# Loginator2368.net
KiCad netlist of a schematic drawn in EAGLE
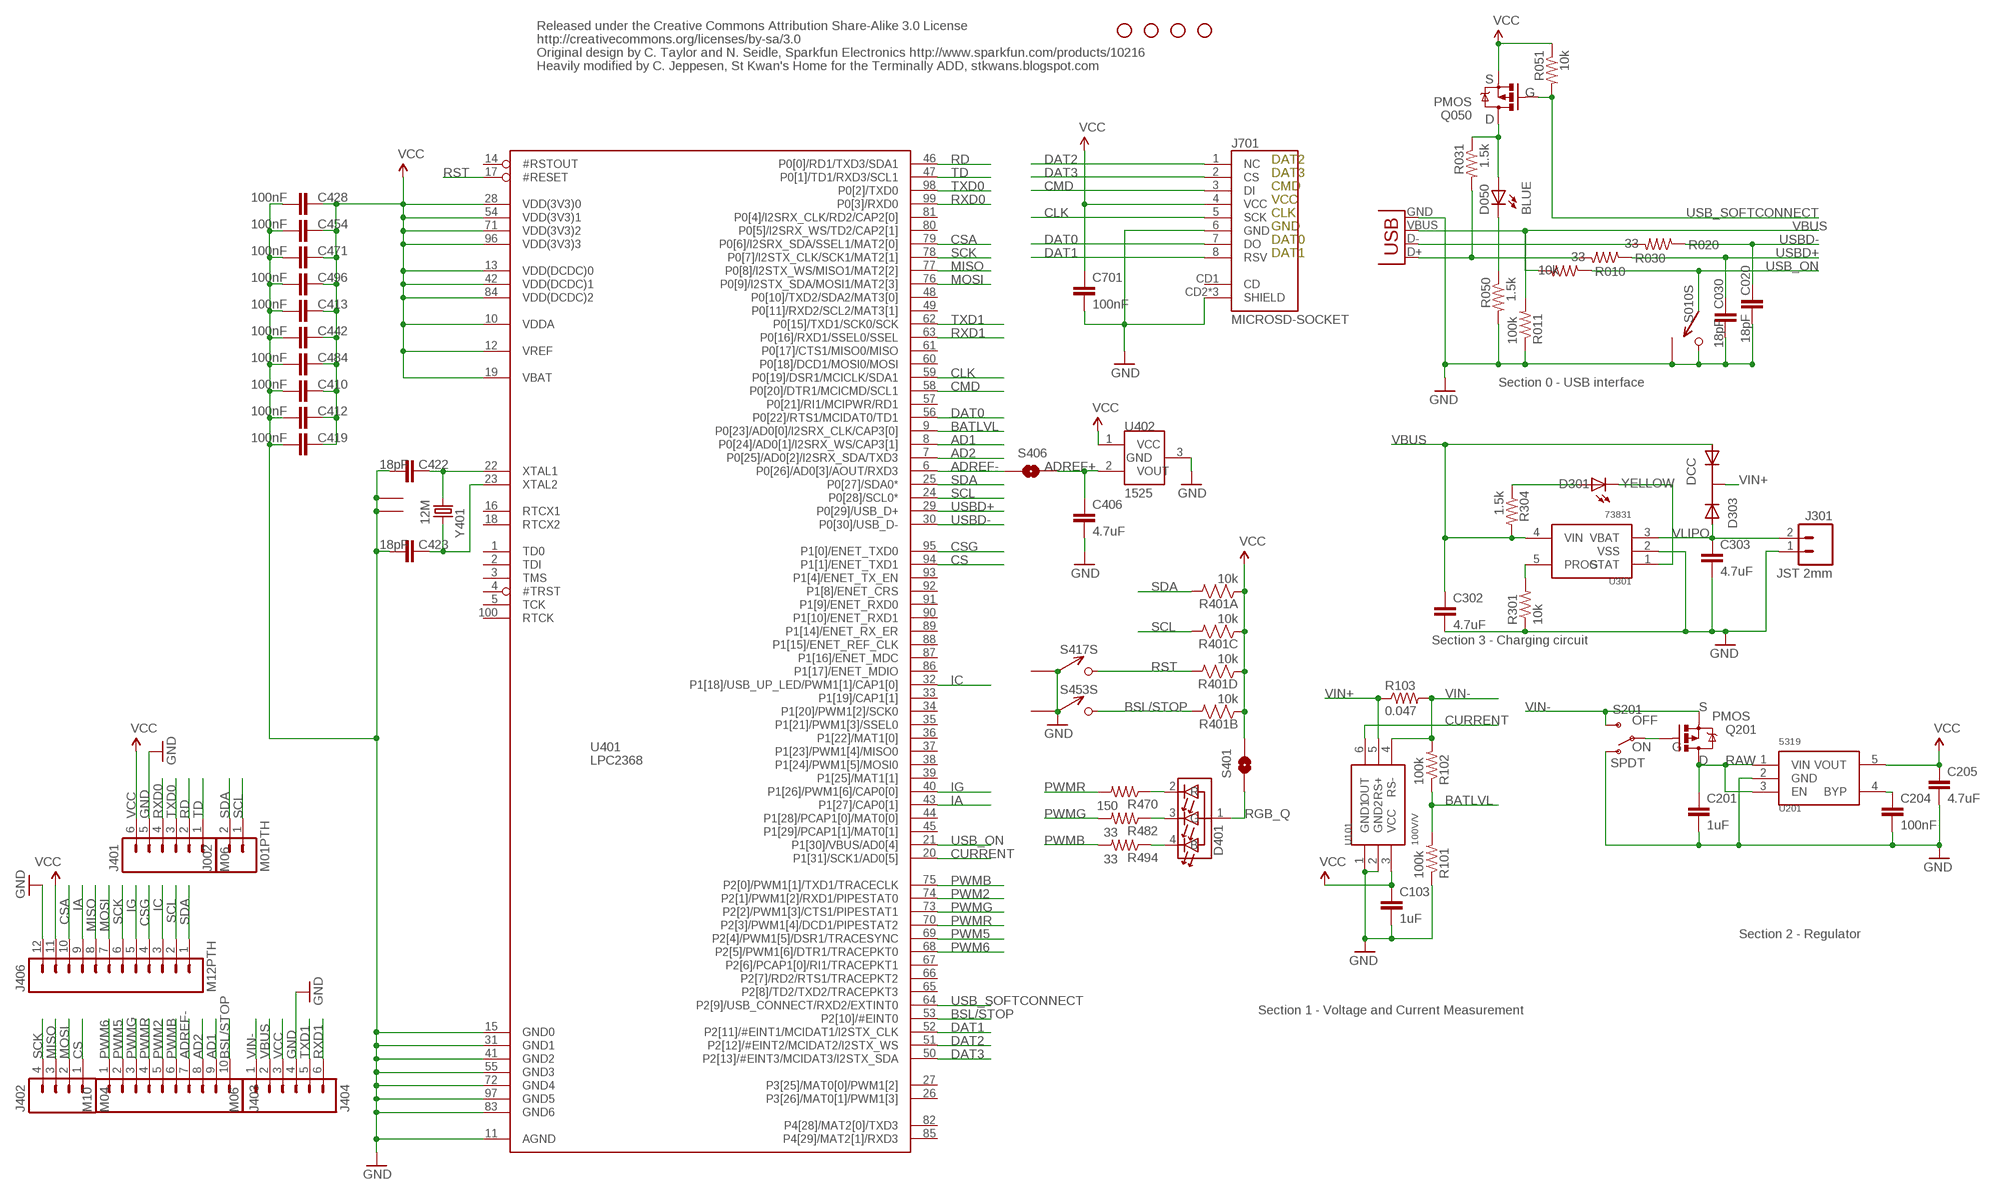
[diagram p0: schematic, sheet 1]

(export (version "E")
  (design (tool "Eeschema 10.0.6"))
  (components
    (comp (ref "C020")
      (value "18pF")
      (footprint "eagle-import:0402-CAP")
      (libsource (lib "eagle-import") (part "CAP0402-CAP"))
    )
    (comp (ref "C030")
      (value "18pF")
      (footprint "eagle-import:0402-CAP")
      (libsource (lib "eagle-import") (part "CAP0402-CAP"))
    )
    (comp (ref "C103")
      (value "1uF")
      (footprint "eagle-import:0402-CAP")
      (libsource (lib "eagle-import") (part "CAP0402-CAP"))
    )
    (comp (ref "C201")
      (value "1uF")
      (footprint "eagle-import:0402-CAP")
      (libsource (lib "eagle-import") (part "CAP0402-CAP"))
    )
    (comp (ref "C204")
      (value "100nF")
      (footprint "eagle-import:0402-CAP")
      (libsource (lib "eagle-import") (part "CAP0402-CAP"))
    )
    (comp (ref "C205")
      (value "4.7uF")
      (footprint "eagle-import:0402-CAP")
      (libsource (lib "eagle-import") (part "CAP0402-CAP"))
    )
    (comp (ref "C302")
      (value "4.7uF")
      (footprint "eagle-import:0402-CAP")
      (libsource (lib "eagle-import") (part "CAP0402-CAP"))
    )
    (comp (ref "C303")
      (value "4.7uF")
      (footprint "eagle-import:0402-CAP")
      (libsource (lib "eagle-import") (part "CAP0402-CAP"))
    )
    (comp (ref "C406")
      (value "4.7uF")
      (footprint "eagle-import:0402-CAP")
      (libsource (lib "eagle-import") (part "CAP0402-CAP"))
    )
    (comp (ref "C410")
      (value "100nF")
      (footprint "eagle-import:0402-CAP")
      (libsource (lib "eagle-import") (part "CAP0402-CAP"))
    )
    (comp (ref "C412")
      (value "100nF")
      (footprint "eagle-import:0402-CAP")
      (libsource (lib "eagle-import") (part "CAP0402-CAP"))
    )
    (comp (ref "C413")
      (value "100nF")
      (footprint "eagle-import:0402-CAP")
      (libsource (lib "eagle-import") (part "CAP0402-CAP"))
    )
    (comp (ref "C419")
      (value "100nF")
      (footprint "eagle-import:0402-CAP")
      (libsource (lib "eagle-import") (part "CAP0402-CAP"))
    )
    (comp (ref "C422")
      (value "18pF")
      (footprint "eagle-import:0402-CAP")
      (libsource (lib "eagle-import") (part "CAP0402-CAP"))
    )
    (comp (ref "C423")
      (value "18pF")
      (footprint "eagle-import:0402-CAP")
      (libsource (lib "eagle-import") (part "CAP0402-CAP"))
    )
    (comp (ref "C428")
      (value "100nF")
      (footprint "eagle-import:0402-CAP")
      (libsource (lib "eagle-import") (part "CAP0402-CAP"))
    )
    (comp (ref "C442")
      (value "100nF")
      (footprint "eagle-import:0402-CAP")
      (libsource (lib "eagle-import") (part "CAP0402-CAP"))
    )
    (comp (ref "C454")
      (value "100nF")
      (footprint "eagle-import:0402-CAP")
      (libsource (lib "eagle-import") (part "CAP0402-CAP"))
    )
    (comp (ref "C471")
      (value "100nF")
      (footprint "eagle-import:0402-CAP")
      (libsource (lib "eagle-import") (part "CAP0402-CAP"))
    )
    (comp (ref "C484")
      (value "100nF")
      (footprint "eagle-import:0402-CAP")
      (libsource (lib "eagle-import") (part "CAP0402-CAP"))
    )
    (comp (ref "C496")
      (value "100nF")
      (footprint "eagle-import:0402-CAP")
      (libsource (lib "eagle-import") (part "CAP0402-CAP"))
    )
    (comp (ref "C701")
      (value "100nF")
      (footprint "eagle-import:0402-CAP")
      (libsource (lib "eagle-import") (part "CAP0402-CAP"))
    )
    (comp (ref "D050")
      (value "BLUE")
      (footprint "eagle-import:LED-0603")
      (libsource (lib "eagle-import") (part "LED0603"))
    )
    (comp (ref "D301")
      (value "YELLOW")
      (footprint "eagle-import:LED-0603")
      (libsource (lib "eagle-import") (part "LED0603"))
    )
    (comp (ref "D303")
      (value "DCC")
      (footprint "eagle-import:SOT-23-3")
      (libsource (lib "eagle-import") (part "PMEG2005CT"))
    )
    (comp (ref "D401")
      (value "RGB")
      (footprint "eagle-import:HSMF-C118")
      (libsource (lib "eagle-import") (part "HSMF-C118"))
    )
    (comp (ref "J001")
      (value "USBSMD")
      (footprint "eagle-import:USB-MINIB")
      (libsource (lib "eagle-import") (part "USBSMD"))
    )
    (comp (ref "J002")
      (value "M01PTH")
      (footprint "eagle-import:1X02")
      (libsource (lib "eagle-import") (part "M02PTH"))
    )
    (comp (ref "J301")
      (value "JST 2mm")
      (footprint "eagle-import:JST-2-SMD")
      (libsource (lib "eagle-import") (part "M02-JST-2MM-SMT"))
    )
    (comp (ref "J401")
      (value "M06")
      (footprint "eagle-import:1X06")
      (libsource (lib "eagle-import") (part "M06SIP"))
    )
    (comp (ref "J402")
      (value "M04")
      (footprint "eagle-import:1X04")
      (libsource (lib "eagle-import") (part "M04PTH"))
    )
    (comp (ref "J403")
      (value "M10")
      (footprint "eagle-import:1X10")
      (libsource (lib "eagle-import") (part "M10{dblquote}"))
    )
    (comp (ref "J404")
      (value "M06")
      (footprint "eagle-import:1X06")
      (libsource (lib "eagle-import") (part "M06SIP"))
    )
    (comp (ref "J406")
      (value "M12PTH")
      (footprint "eagle-import:1X12")
      (libsource (lib "eagle-import") (part "M12PTH"))
    )
    (comp (ref "J701")
      (value "MICROSD-SOCKET")
      (footprint "eagle-import:MICROSD-SOCKET-PP")
      (libsource (lib "eagle-import") (part "MICROSD-SOCKET"))
    )
    (comp (ref "JP1")
      (value "STAND-OFF")
      (footprint "eagle-import:STAND-OFF")
      (libsource (lib "eagle-import") (part "STAND-OFF"))
    )
    (comp (ref "JP2")
      (value "STAND-OFF")
      (footprint "eagle-import:STAND-OFF")
      (libsource (lib "eagle-import") (part "STAND-OFF"))
    )
    (comp (ref "JP3")
      (value "STAND-OFF")
      (footprint "eagle-import:STAND-OFF")
      (libsource (lib "eagle-import") (part "STAND-OFF"))
    )
    (comp (ref "JP4")
      (value "STAND-OFF")
      (footprint "eagle-import:STAND-OFF")
      (libsource (lib "eagle-import") (part "STAND-OFF"))
    )
    (comp (ref "Q050")
      (value "PMOS")
      (footprint "eagle-import:SOT23-3")
      (libsource (lib "eagle-import") (part "MOSFET-PCHANNELSMD"))
    )
    (comp (ref "Q201")
      (value "PMOS")
      (footprint "eagle-import:SOT23-3")
      (libsource (lib "eagle-import") (part "MOSFET-PCHANNELSMD"))
    )
    (comp (ref "R010")
      (value "10k")
      (footprint "eagle-import:0402-RES")
      (libsource (lib "eagle-import") (part "RESISTOR0402-RES"))
    )
    (comp (ref "R011")
      (value "100k")
      (footprint "eagle-import:0402-RES")
      (libsource (lib "eagle-import") (part "RESISTOR0402-RES"))
    )
    (comp (ref "R020")
      (value "33")
      (footprint "eagle-import:0402-RES")
      (libsource (lib "eagle-import") (part "RESISTOR0402-RES"))
    )
    (comp (ref "R030")
      (value "33")
      (footprint "eagle-import:0402-RES")
      (libsource (lib "eagle-import") (part "RESISTOR0402-RES"))
    )
    (comp (ref "R031")
      (value "1.5k")
      (footprint "eagle-import:0402-RES")
      (libsource (lib "eagle-import") (part "RESISTOR0402-RES"))
    )
    (comp (ref "R050")
      (value "1.5k")
      (footprint "eagle-import:0402-RES")
      (libsource (lib "eagle-import") (part "RESISTOR0402-RES"))
    )
    (comp (ref "R051")
      (value "10k")
      (footprint "eagle-import:0402-RES")
      (libsource (lib "eagle-import") (part "RESISTOR0402-RES"))
    )
    (comp (ref "R101")
      (value "100k")
      (footprint "eagle-import:0402-RES")
      (libsource (lib "eagle-import") (part "RESISTOR0402-RES"))
    )
    (comp (ref "R102")
      (value "100k")
      (footprint "eagle-import:0402-RES")
      (libsource (lib "eagle-import") (part "RESISTOR0402-RES"))
    )
    (comp (ref "R103")
      (value "0.047")
      (footprint "eagle-import:0402-RES")
      (libsource (lib "eagle-import") (part "RESISTOR0402-RES"))
    )
    (comp (ref "R301")
      (value "10k")
      (footprint "eagle-import:0402-RES")
      (libsource (lib "eagle-import") (part "RESISTOR0402-RES"))
    )
    (comp (ref "R304")
      (value "1.5k")
      (footprint "eagle-import:0402-RES")
      (libsource (lib "eagle-import") (part "RESISTOR0402-RES"))
    )
    (comp (ref "R401")
      (value "10k")
      (footprint "eagle-import:CRA04")
      (libsource (lib "eagle-import") (part "RP404"))
    )
    (comp (ref "R470")
      (value "150")
      (footprint "eagle-import:0402-RES")
      (libsource (lib "eagle-import") (part "RESISTOR0402-RES"))
    )
    (comp (ref "R482")
      (value "33")
      (footprint "eagle-import:0402-RES")
      (libsource (lib "eagle-import") (part "RESISTOR0402-RES"))
    )
    (comp (ref "R494")
      (value "33")
      (footprint "eagle-import:0402-RES")
      (libsource (lib "eagle-import") (part "RESISTOR0402-RES"))
    )
    (comp (ref "S010")
      (value "SPST")
      (footprint "eagle-import:B3U-1100P")
      (libsource (lib "eagle-import") (part "B3U-1100P"))
    )
    (comp (ref "S201")
      (value "SPDT")
      (footprint "eagle-import:AYZ0202")
      (libsource (lib "eagle-import") (part "SWITCH-SPSTSMD"))
    )
    (comp (ref "S401")
      (value "SOLDERJUMPERNO")
      (footprint "eagle-import:SJ_2S-NO")
      (libsource (lib "eagle-import") (part "SOLDERJUMPERNO"))
    )
    (comp (ref "S406")
      (value "SOLDERJUMPERNO")
      (footprint "eagle-import:SJ_2S-NO")
      (libsource (lib "eagle-import") (part "SOLDERJUMPERNO"))
    )
    (comp (ref "S417")
      (value "SPST")
      (footprint "eagle-import:B3U-1100P")
      (libsource (lib "eagle-import") (part "B3U-1100P"))
    )
    (comp (ref "S453")
      (value "SPST")
      (footprint "eagle-import:B3U-1100P")
      (libsource (lib "eagle-import") (part "B3U-1100P"))
    )
    (comp (ref "U101")
      (value "100V/V")
      (footprint "eagle-import:SOT-23-6")
      (libsource (lib "eagle-import") (part "MAX4173"))
    )
    (comp (ref "U201")
      (value "5319")
      (footprint "eagle-import:SOT-23-5")
      (libsource (lib "eagle-import") (part "MIC5319D5"))
    )
    (comp (ref "U301")
      (value "73831")
      (footprint "eagle-import:SOT-23-5")
      (libsource (lib "eagle-import") (part "MCP73831"))
    )
    (comp (ref "U401")
      (value "LPC2368")
      (footprint "eagle-import:LQFP100")
      (libsource (lib "eagle-import") (part "LPC2368"))
    )
    (comp (ref "U402")
      (value "1525")
      (footprint "eagle-import:SOT-23-3")
      (libsource (lib "eagle-import") (part "MCP1525"))
    )
    (comp (ref "Y401")
      (value "12M")
      (footprint "eagle-import:CRYSTAL_SMD")
      (libsource (lib "eagle-import") (part "TSX-3225"))
    )
  )
  (nets
    (net (code "1") (name "/AD1") (class "Default")
      (node (ref "J403") (pin "9") (pinfunction "9_9") (pintype "passive"))
      (node (ref "U401") (pin "8") (pinfunction "P0[24]/AD0[1]/I2SRX_WS/CAP3[1]_8") (pintype "bidirectional"))
    )
    (net (code "2") (name "/AD2") (class "Default")
      (node (ref "J403") (pin "8") (pinfunction "8_8") (pintype "passive"))
      (node (ref "U401") (pin "7") (pinfunction "P0[25]/AD0[2]/I2SRX_SDA/TXD3_7") (pintype "bidirectional"))
    )
    (net (code "3") (name "/ADREF+") (class "Default")
      (node (ref "C406") (pin "1") (pinfunction "1_1") (pintype "passive"))
      (node (ref "S406") (pin "1") (pinfunction "1_1") (pintype "passive"))
      (node (ref "U402") (pin "2") (pinfunction "VOUT_2") (pintype "bidirectional"))
    )
    (net (code "4") (name "/ADREF-") (class "Default")
      (node (ref "J403") (pin "7") (pinfunction "7_7") (pintype "passive"))
      (node (ref "S406") (pin "2") (pinfunction "2_2") (pintype "passive"))
      (node (ref "U401") (pin "6") (pinfunction "P0[26]/AD0[3]/AOUT/RXD3_6") (pintype "bidirectional"))
    )
    (net (code "5") (name "/BATLVL") (class "Default")
      (node (ref "R101") (pin "2") (pinfunction "2_2") (pintype "passive"))
      (node (ref "R102") (pin "1") (pinfunction "1_1") (pintype "passive"))
      (node (ref "U401") (pin "9") (pinfunction "P0[23]/AD0[0]/I2SRX_CLK/CAP3[0]_9") (pintype "bidirectional"))
    )
    (net (code "6") (name "/BSL{slash}STOP") (class "Default")
      (node (ref "J403") (pin "10") (pinfunction "10_10") (pintype "passive"))
      (node (ref "R401") (pin "7") (pinfunction "2_7") (pintype "passive"))
      (node (ref "S453") (pin "P$2") (pinfunction "2_P$2") (pintype "bidirectional"))
      (node (ref "U401") (pin "53") (pinfunction "P2[10]/#EINT0_53") (pintype "bidirectional"))
    )
    (net (code "7") (name "/CLK") (class "Default")
      (node (ref "J701") (pin "5") (pinfunction "SCK_5") (pintype "bidirectional"))
      (node (ref "U401") (pin "59") (pinfunction "P0[19]/DSR1/MCICLK/SDA1_59") (pintype "bidirectional"))
    )
    (net (code "8") (name "/CMD") (class "Default")
      (node (ref "J701") (pin "3") (pinfunction "DI_3") (pintype "bidirectional"))
      (node (ref "U401") (pin "58") (pinfunction "P0[20]/DTR1/MCICMD/SCL1_58") (pintype "bidirectional"))
    )
    (net (code "9") (name "/CS") (class "Default")
      (node (ref "J402") (pin "1") (pinfunction "1_1") (pintype "passive"))
      (node (ref "U401") (pin "94") (pinfunction "P1[1]/ENET_TXD1_94") (pintype "bidirectional"))
    )
    (net (code "10") (name "/CSA") (class "Default")
      (node (ref "J406") (pin "10") (pinfunction "10_10") (pintype "passive"))
      (node (ref "U401") (pin "79") (pinfunction "P0[6]/I2SRX_SDA/SSEL1/MAT2[0]_79") (pintype "bidirectional"))
    )
    (net (code "11") (name "/CSG") (class "Default")
      (node (ref "J406") (pin "4") (pinfunction "4_4") (pintype "passive"))
      (node (ref "U401") (pin "95") (pinfunction "P1[0]/ENET_TXD0_95") (pintype "bidirectional"))
    )
    (net (code "12") (name "/CURRENT") (class "Default")
      (node (ref "U101") (pin "6") (pinfunction "OUT_6") (pintype "bidirectional"))
      (node (ref "U401") (pin "20") (pinfunction "P1[31]/SCK1/AD0[5]_20") (pintype "bidirectional"))
    )
    (net (code "13") (name "/DAT0") (class "Default")
      (node (ref "J701") (pin "7") (pinfunction "DO_7") (pintype "bidirectional"))
      (node (ref "U401") (pin "56") (pinfunction "P0[22]/RTS1/MCIDAT0/TD1_56") (pintype "bidirectional"))
    )
    (net (code "14") (name "/DAT1") (class "Default")
      (node (ref "J701") (pin "8") (pinfunction "RSV_8") (pintype "bidirectional"))
      (node (ref "U401") (pin "52") (pinfunction "P2[11]/#EINT1/MCIDAT1/I2STX_CLK_52") (pintype "bidirectional"))
    )
    (net (code "15") (name "/DAT2") (class "Default")
      (node (ref "J701") (pin "1") (pinfunction "NC_1") (pintype "bidirectional"))
      (node (ref "U401") (pin "51") (pinfunction "P2[12]/#EINT2/MCIDAT2/I2STX_WS_51") (pintype "bidirectional"))
    )
    (net (code "16") (name "/DAT3") (class "Default")
      (node (ref "J701") (pin "2") (pinfunction "CS_2") (pintype "bidirectional"))
      (node (ref "U401") (pin "50") (pinfunction "P2[13]/#EINT3/MCIDAT3/I2STX_SDA_50") (pintype "bidirectional"))
    )
    (net (code "17") (name "/IA") (class "Default")
      (node (ref "J406") (pin "9") (pinfunction "9_9") (pintype "passive"))
      (node (ref "U401") (pin "43") (pinfunction "P1[27]/CAP0[1]_43") (pintype "bidirectional"))
    )
    (net (code "18") (name "/IC") (class "Default")
      (node (ref "J406") (pin "3") (pinfunction "3_3") (pintype "passive"))
      (node (ref "U401") (pin "32") (pinfunction "P1[18]/USB_UP_LED/PWM1[1]/CAP1[0]_32") (pintype "bidirectional"))
    )
    (net (code "19") (name "/IG") (class "Default")
      (node (ref "J406") (pin "5") (pinfunction "5_5") (pintype "passive"))
      (node (ref "U401") (pin "40") (pinfunction "P1[26]/PWM1[6]/CAP0[0]_40") (pintype "bidirectional"))
    )
    (net (code "20") (name "/MISO") (class "Default")
      (node (ref "J402") (pin "3") (pinfunction "3_3") (pintype "passive"))
      (node (ref "J406") (pin "8") (pinfunction "8_8") (pintype "passive"))
      (node (ref "U401") (pin "77") (pinfunction "P0[8]/I2STX_WS/MISO1/MAT2[2]_77") (pintype "bidirectional"))
    )
    (net (code "21") (name "/MOSI") (class "Default")
      (node (ref "J402") (pin "2") (pinfunction "2_2") (pintype "passive"))
      (node (ref "J406") (pin "7") (pinfunction "7_7") (pintype "passive"))
      (node (ref "U401") (pin "76") (pinfunction "P0[9]/I2STX_SDA/MOSI1/MAT2[3]_76") (pintype "bidirectional"))
    )
    (net (code "22") (name "/PWM2") (class "Default")
      (node (ref "J403") (pin "5") (pinfunction "5_5") (pintype "passive"))
      (node (ref "U401") (pin "74") (pinfunction "P2[1]/PWM1[2]/RXD1/PIPESTAT0_74") (pintype "bidirectional"))
    )
    (net (code "23") (name "/PWM5") (class "Default")
      (node (ref "J403") (pin "2") (pinfunction "2_2") (pintype "passive"))
      (node (ref "U401") (pin "69") (pinfunction "P2[4]/PWM1[5]/DSR1/TRACESYNC_69") (pintype "bidirectional"))
    )
    (net (code "24") (name "/PWM6") (class "Default")
      (node (ref "J403") (pin "1") (pinfunction "1_1") (pintype "passive"))
      (node (ref "U401") (pin "68") (pinfunction "P2[5]/PWM1[6]/DTR1/TRACEPKT0_68") (pintype "bidirectional"))
    )
    (net (code "25") (name "/PWMB") (class "Default")
      (node (ref "J403") (pin "6") (pinfunction "6_6") (pintype "passive"))
      (node (ref "R494") (pin "2") (pinfunction "2_2") (pintype "passive"))
      (node (ref "U401") (pin "75") (pinfunction "P2[0]/PWM1[1]/TXD1/TRACECLK_75") (pintype "bidirectional"))
    )
    (net (code "26") (name "/PWMG") (class "Default")
      (node (ref "J403") (pin "3") (pinfunction "3_3") (pintype "passive"))
      (node (ref "R482") (pin "2") (pinfunction "2_2") (pintype "passive"))
      (node (ref "U401") (pin "73") (pinfunction "P2[2]/PWM1[3]/CTS1/PIPESTAT1_73") (pintype "bidirectional"))
    )
    (net (code "27") (name "/PWMR") (class "Default")
      (node (ref "J403") (pin "4") (pinfunction "4_4") (pintype "passive"))
      (node (ref "R470") (pin "2") (pinfunction "2_2") (pintype "passive"))
      (node (ref "U401") (pin "70") (pinfunction "P2[3]/PWM1[4]/DCD1/PIPESTAT2_70") (pintype "bidirectional"))
    )
    (net (code "28") (name "/RAW") (class "Default")
      (node (ref "C201") (pin "1") (pinfunction "1_1") (pintype "passive"))
      (node (ref "Q201") (pin "3") (pinfunction "D_3") (pintype "passive"))
      (node (ref "U201") (pin "1") (pinfunction "VIN_1") (pintype "bidirectional"))
      (node (ref "U201") (pin "3") (pinfunction "EN_3") (pintype "bidirectional"))
    )
    (net (code "29") (name "/RD") (class "Default")
      (node (ref "J401") (pin "2") (pinfunction "2_2") (pintype "passive"))
      (node (ref "U401") (pin "46") (pinfunction "P0[0]/RD1/TXD3/SDA1_46") (pintype "bidirectional"))
    )
    (net (code "30") (name "/RGB_Q") (class "Default")
      (node (ref "D401") (pin "1") (pinfunction "A_1") (pintype "passive"))
      (node (ref "S401") (pin "1") (pinfunction "1_1") (pintype "passive"))
    )
    (net (code "31") (name "/RST") (class "Default")
      (node (ref "R401") (pin "5") (pinfunction "2_5") (pintype "passive"))
      (node (ref "S417") (pin "P$2") (pinfunction "2_P$2") (pintype "bidirectional"))
      (node (ref "U401") (pin "17") (pinfunction "#RESET_17") (pintype "bidirectional"))
    )
    (net (code "32") (name "/RXD0") (class "Default")
      (node (ref "J401") (pin "4") (pinfunction "4_4") (pintype "passive"))
      (node (ref "U401") (pin "99") (pinfunction "P0[3]/RXD0_99") (pintype "bidirectional"))
    )
    (net (code "33") (name "/RXD1") (class "Default")
      (node (ref "J404") (pin "6") (pinfunction "6_6") (pintype "passive"))
      (node (ref "U401") (pin "63") (pinfunction "P0[16]/RXD1/SSEL0/SSEL_63") (pintype "bidirectional"))
    )
    (net (code "34") (name "/SCK") (class "Default")
      (node (ref "J402") (pin "4") (pinfunction "4_4") (pintype "passive"))
      (node (ref "J406") (pin "6") (pinfunction "6_6") (pintype "passive"))
      (node (ref "U401") (pin "78") (pinfunction "P0[7]/I2STX_CLK/SCK1/MAT2[1]_78") (pintype "bidirectional"))
    )
    (net (code "35") (name "/SCL") (class "Default")
      (node (ref "J002") (pin "1") (pinfunction "1_1") (pintype "passive"))
      (node (ref "J406") (pin "2") (pinfunction "2_2") (pintype "passive"))
      (node (ref "R401") (pin "6") (pinfunction "2_6") (pintype "passive"))
      (node (ref "U401") (pin "24") (pinfunction "P0[28]/SCL0*_24") (pintype "bidirectional"))
    )
    (net (code "36") (name "/SDA") (class "Default")
      (node (ref "J002") (pin "2") (pinfunction "2_2") (pintype "passive"))
      (node (ref "J406") (pin "1") (pinfunction "1_1") (pintype "passive"))
      (node (ref "R401") (pin "8") (pinfunction "2_8") (pintype "passive"))
      (node (ref "U401") (pin "25") (pinfunction "P0[27]/SDA0*_25") (pintype "bidirectional"))
    )
    (net (code "37") (name "/TD") (class "Default")
      (node (ref "J401") (pin "1") (pinfunction "1_1") (pintype "passive"))
      (node (ref "U401") (pin "47") (pinfunction "P0[1]/TD1/RXD3/SCL1_47") (pintype "bidirectional"))
    )
    (net (code "38") (name "/TXD0") (class "Default")
      (node (ref "J401") (pin "3") (pinfunction "3_3") (pintype "passive"))
      (node (ref "U401") (pin "98") (pinfunction "P0[2]/TXD0_98") (pintype "bidirectional"))
    )
    (net (code "39") (name "/TXD1") (class "Default")
      (node (ref "J404") (pin "5") (pinfunction "5_5") (pintype "passive"))
      (node (ref "U401") (pin "62") (pinfunction "P0[15]/TXD1/SCK0/SCK_62") (pintype "bidirectional"))
    )
    (net (code "40") (name "/USBD+") (class "Default")
      (node (ref "C030") (pin "1") (pinfunction "1_1") (pintype "passive"))
      (node (ref "R030") (pin "1") (pinfunction "1_1") (pintype "passive"))
      (node (ref "U401") (pin "29") (pinfunction "P0[29]/USB_D+_29") (pintype "bidirectional"))
    )
    (net (code "41") (name "/USBD-") (class "Default")
      (node (ref "C020") (pin "1") (pinfunction "1_1") (pintype "passive"))
      (node (ref "R020") (pin "1") (pinfunction "1_1") (pintype "passive"))
      (node (ref "U401") (pin "30") (pinfunction "P0[30]/USB_D-_30") (pintype "bidirectional"))
    )
    (net (code "42") (name "/USB_ON") (class "Default")
      (node (ref "R010") (pin "1") (pinfunction "1_1") (pintype "passive"))
      (node (ref "S010") (pin "P$1") (pinfunction "1_P$1") (pintype "bidirectional"))
      (node (ref "U401") (pin "21") (pinfunction "P1[30]/VBUS/AD0[4]_21") (pintype "bidirectional"))
    )
    (net (code "43") (name "/USB_SOFTCONNECT") (class "Default")
      (node (ref "Q050") (pin "1") (pinfunction "G_1") (pintype "passive"))
      (node (ref "R051") (pin "2") (pinfunction "2_2") (pintype "passive"))
      (node (ref "U401") (pin "64") (pinfunction "P2[9]/USB_CONNECT/RXD2/EXTINT0_64") (pintype "bidirectional"))
    )
    (net (code "44") (name "/VBUS") (class "Default")
      (node (ref "C302") (pin "1") (pinfunction "1_1") (pintype "passive"))
      (node (ref "D303") (pin "1") (pinfunction "A1_1") (pintype "passive"))
      (node (ref "J001") (pin "VBUS") (pinfunction "VBUS_VBUS") (pintype "bidirectional"))
      (node (ref "J404") (pin "2") (pinfunction "2_2") (pintype "passive"))
      (node (ref "R010") (pin "2") (pinfunction "2_2") (pintype "passive"))
      (node (ref "R011") (pin "2") (pinfunction "2_2") (pintype "passive"))
      (node (ref "R304") (pin "2") (pinfunction "2_2") (pintype "passive"))
      (node (ref "U301") (pin "4") (pinfunction "VIN_4") (pintype "bidirectional"))
    )
    (net (code "45") (name "/VIN+") (class "Default")
      (node (ref "D303") (pin "3") (pinfunction "K_3") (pintype "passive"))
      (node (ref "R103") (pin "1") (pinfunction "1_1") (pintype "passive"))
      (node (ref "U101") (pin "5") (pinfunction "RS+_5") (pintype "bidirectional"))
    )
    (net (code "46") (name "/VIN-") (class "Default")
      (node (ref "J404") (pin "1") (pinfunction "1_1") (pintype "passive"))
      (node (ref "Q201") (pin "2") (pinfunction "S_2") (pintype "passive"))
      (node (ref "R102") (pin "2") (pinfunction "2_2") (pintype "passive"))
      (node (ref "R103") (pin "2") (pinfunction "2_2") (pintype "passive"))
      (node (ref "S201") (pin "3") (pinfunction "S_3") (pintype "passive"))
      (node (ref "U101") (pin "4") (pinfunction "RS-_4") (pintype "bidirectional"))
    )
    (net (code "47") (name "/VLIPO") (class "Default")
      (node (ref "C303") (pin "1") (pinfunction "1_1") (pintype "passive"))
      (node (ref "D303") (pin "2") (pinfunction "A2_2") (pintype "passive"))
      (node (ref "J301") (pin "2") (pinfunction "2_2") (pintype "passive"))
      (node (ref "U301") (pin "3") (pinfunction "VBAT_3") (pintype "bidirectional"))
    )
    (net (code "48") (name "GND") (class "Default")
      (node (ref "C020") (pin "2") (pinfunction "2_2") (pintype "passive"))
      (node (ref "C030") (pin "2") (pinfunction "2_2") (pintype "passive"))
      (node (ref "C103") (pin "2") (pinfunction "2_2") (pintype "passive"))
      (node (ref "C201") (pin "2") (pinfunction "2_2") (pintype "passive"))
      (node (ref "C204") (pin "2") (pinfunction "2_2") (pintype "passive"))
      (node (ref "C205") (pin "2") (pinfunction "2_2") (pintype "passive"))
      (node (ref "C302") (pin "2") (pinfunction "2_2") (pintype "passive"))
      (node (ref "C303") (pin "2") (pinfunction "2_2") (pintype "passive"))
      (node (ref "C406") (pin "2") (pinfunction "2_2") (pintype "passive"))
      (node (ref "C410") (pin "2") (pinfunction "2_2") (pintype "passive"))
      (node (ref "C412") (pin "2") (pinfunction "2_2") (pintype "passive"))
      (node (ref "C413") (pin "2") (pinfunction "2_2") (pintype "passive"))
      (node (ref "C419") (pin "2") (pinfunction "2_2") (pintype "passive"))
      (node (ref "C422") (pin "1") (pinfunction "1_1") (pintype "passive"))
      (node (ref "C423") (pin "1") (pinfunction "1_1") (pintype "passive"))
      (node (ref "C428") (pin "2") (pinfunction "2_2") (pintype "passive"))
      (node (ref "C442") (pin "2") (pinfunction "2_2") (pintype "passive"))
      (node (ref "C454") (pin "2") (pinfunction "2_2") (pintype "passive"))
      (node (ref "C471") (pin "2") (pinfunction "2_2") (pintype "passive"))
      (node (ref "C484") (pin "2") (pinfunction "2_2") (pintype "passive"))
      (node (ref "C496") (pin "2") (pinfunction "2_2") (pintype "passive"))
      (node (ref "C701") (pin "2") (pinfunction "2_2") (pintype "passive"))
      (node (ref "J001") (pin "GND") (pinfunction "GND_GND") (pintype "bidirectional"))
      (node (ref "J301") (pin "1") (pinfunction "1_1") (pintype "passive"))
      (node (ref "J401") (pin "5") (pinfunction "5_5") (pintype "passive"))
      (node (ref "J404") (pin "4") (pinfunction "4_4") (pintype "passive"))
      (node (ref "J406") (pin "12") (pinfunction "12_12") (pintype "passive"))
      (node (ref "J701") (pin "6") (pinfunction "GND_6") (pintype "bidirectional"))
      (node (ref "J701") (pin "CD2") (pinfunction "SHIELD_CD2") (pintype "bidirectional"))
      (node (ref "J701") (pin "GND1") (pinfunction "SHIELD_GND1") (pintype "bidirectional"))
      (node (ref "J701") (pin "GND3") (pinfunction "SHIELD_GND3") (pintype "bidirectional"))
      (node (ref "R011") (pin "1") (pinfunction "1_1") (pintype "passive"))
      (node (ref "R050") (pin "2") (pinfunction "2_2") (pintype "passive"))
      (node (ref "R101") (pin "1") (pinfunction "1_1") (pintype "passive"))
      (node (ref "R301") (pin "1") (pinfunction "1_1") (pintype "passive"))
      (node (ref "S010") (pin "P$2") (pinfunction "2_P$2") (pintype "bidirectional"))
      (node (ref "S010") (pin "P$3") (pinfunction "1_P$3") (pintype "bidirectional"))
      (node (ref "S201") (pin "1") (pinfunction "O_1") (pintype "passive"))
      (node (ref "S417") (pin "P$1") (pinfunction "1_P$1") (pintype "bidirectional"))
      (node (ref "S417") (pin "P$3") (pinfunction "1_P$3") (pintype "bidirectional"))
      (node (ref "S453") (pin "P$1") (pinfunction "1_P$1") (pintype "bidirectional"))
      (node (ref "S453") (pin "P$3") (pinfunction "1_P$3") (pintype "bidirectional"))
      (node (ref "U101") (pin "1") (pinfunction "GND1_1") (pintype "bidirectional"))
      (node (ref "U101") (pin "2") (pinfunction "GND2_2") (pintype "bidirectional"))
      (node (ref "U201") (pin "2") (pinfunction "GND_2") (pintype "bidirectional"))
      (node (ref "U301") (pin "2") (pinfunction "VSS_2") (pintype "bidirectional"))
      (node (ref "U401") (pin "11") (pinfunction "AGND_11") (pintype "bidirectional"))
      (node (ref "U401") (pin "15") (pinfunction "GND0_15") (pintype "bidirectional"))
      (node (ref "U401") (pin "31") (pinfunction "GND1_31") (pintype "bidirectional"))
      (node (ref "U401") (pin "41") (pinfunction "GND2_41") (pintype "bidirectional"))
      (node (ref "U401") (pin "55") (pinfunction "GND3_55") (pintype "bidirectional"))
      (node (ref "U401") (pin "72") (pinfunction "GND4_72") (pintype "bidirectional"))
      (node (ref "U401") (pin "83") (pinfunction "GND6_83") (pintype "bidirectional"))
      (node (ref "U401") (pin "97") (pinfunction "GND5_97") (pintype "bidirectional"))
      (node (ref "U402") (pin "3") (pinfunction "GND_3") (pintype "bidirectional"))
      (node (ref "Y401") (pin "2") (pinfunction "1_2") (pintype "bidirectional"))
      (node (ref "Y401") (pin "4") (pinfunction "1_4") (pintype "bidirectional"))
    )
    (net (code "49") (name "Net-(D050-PadC)") (class "Default")
      (node (ref "D050") (pin "C") (pinfunction "C_C") (pintype "passive"))
      (node (ref "R050") (pin "1") (pinfunction "1_1") (pintype "passive"))
    )
    (net (code "50") (name "Net-(D301-PadA)") (class "Default")
      (node (ref "D301") (pin "A") (pinfunction "A_A") (pintype "passive"))
      (node (ref "R304") (pin "1") (pinfunction "1_1") (pintype "passive"))
    )
    (net (code "51") (name "Net-(D401-B)") (class "Default")
      (node (ref "D401") (pin "4") (pinfunction "B_4") (pintype "passive"))
      (node (ref "R494") (pin "1") (pinfunction "1_1") (pintype "passive"))
    )
    (net (code "52") (name "Net-(D401-G)") (class "Default")
      (node (ref "D401") (pin "3") (pinfunction "G_3") (pintype "passive"))
      (node (ref "R482") (pin "1") (pinfunction "1_1") (pintype "passive"))
    )
    (net (code "53") (name "Net-(D401-R)") (class "Default")
      (node (ref "D401") (pin "2") (pinfunction "R_2") (pintype "passive"))
      (node (ref "R470") (pin "1") (pinfunction "1_1") (pintype "passive"))
    )
    (net (code "54") (name "Net-(J001-PadD+)") (class "Default")
      (node (ref "J001") (pin "D+") (pinfunction "D+_D+") (pintype "bidirectional"))
      (node (ref "R030") (pin "2") (pinfunction "2_2") (pintype "passive"))
      (node (ref "R031") (pin "2") (pinfunction "2_2") (pintype "passive"))
    )
    (net (code "55") (name "Net-(J001-PadD-)") (class "Default")
      (node (ref "J001") (pin "D-") (pinfunction "D-_D-") (pintype "bidirectional"))
      (node (ref "R020") (pin "2") (pinfunction "2_2") (pintype "passive"))
    )
    (net (code "56") (name "Net-(Q050-D)") (class "Default")
      (node (ref "D050") (pin "A") (pinfunction "A_A") (pintype "passive"))
      (node (ref "Q050") (pin "3") (pinfunction "D_3") (pintype "passive"))
      (node (ref "R031") (pin "1") (pinfunction "1_1") (pintype "passive"))
    )
    (net (code "57") (name "Net-(Q201-G)") (class "Default")
      (node (ref "Q201") (pin "1") (pinfunction "G_1") (pintype "passive"))
      (node (ref "S201") (pin "2") (pinfunction "P_2") (pintype "passive"))
    )
    (net (code "58") (name "Net-(U201-BYP)") (class "Default")
      (node (ref "C204") (pin "1") (pinfunction "1_1") (pintype "passive"))
      (node (ref "U201") (pin "4") (pinfunction "BYP_4") (pintype "bidirectional"))
    )
    (net (code "59") (name "Net-(U301-PROG)") (class "Default")
      (node (ref "R301") (pin "2") (pinfunction "2_2") (pintype "passive"))
      (node (ref "U301") (pin "5") (pinfunction "PROG_5") (pintype "bidirectional"))
    )
    (net (code "60") (name "Net-(U301-STAT)") (class "Default")
      (node (ref "D301") (pin "C") (pinfunction "C_C") (pintype "passive"))
      (node (ref "U301") (pin "1") (pinfunction "STAT_1") (pintype "bidirectional"))
    )
    (net (code "61") (name "Net-(U401-XTAL1)") (class "Default")
      (node (ref "C422") (pin "2") (pinfunction "2_2") (pintype "passive"))
      (node (ref "U401") (pin "22") (pinfunction "XTAL1_22") (pintype "bidirectional"))
      (node (ref "Y401") (pin "3") (pinfunction "2_3") (pintype "passive"))
    )
    (net (code "62") (name "Net-(U401-XTAL2)") (class "Default")
      (node (ref "C423") (pin "2") (pinfunction "2_2") (pintype "passive"))
      (node (ref "U401") (pin "23") (pinfunction "XTAL2_23") (pintype "bidirectional"))
      (node (ref "Y401") (pin "1") (pinfunction "1_1") (pintype "passive"))
    )
    (net (code "63") (name "VCC") (class "Default")
      (node (ref "C103") (pin "1") (pinfunction "1_1") (pintype "passive"))
      (node (ref "C205") (pin "1") (pinfunction "1_1") (pintype "passive"))
      (node (ref "C410") (pin "1") (pinfunction "1_1") (pintype "passive"))
      (node (ref "C412") (pin "1") (pinfunction "1_1") (pintype "passive"))
      (node (ref "C413") (pin "1") (pinfunction "1_1") (pintype "passive"))
      (node (ref "C419") (pin "1") (pinfunction "1_1") (pintype "passive"))
      (node (ref "C428") (pin "1") (pinfunction "1_1") (pintype "passive"))
      (node (ref "C442") (pin "1") (pinfunction "1_1") (pintype "passive"))
      (node (ref "C454") (pin "1") (pinfunction "1_1") (pintype "passive"))
      (node (ref "C471") (pin "1") (pinfunction "1_1") (pintype "passive"))
      (node (ref "C484") (pin "1") (pinfunction "1_1") (pintype "passive"))
      (node (ref "C496") (pin "1") (pinfunction "1_1") (pintype "passive"))
      (node (ref "C701") (pin "1") (pinfunction "1_1") (pintype "passive"))
      (node (ref "J401") (pin "6") (pinfunction "6_6") (pintype "passive"))
      (node (ref "J404") (pin "3") (pinfunction "3_3") (pintype "passive"))
      (node (ref "J406") (pin "11") (pinfunction "11_11") (pintype "passive"))
      (node (ref "J701") (pin "4") (pinfunction "VCC_4") (pintype "bidirectional"))
      (node (ref "Q050") (pin "2") (pinfunction "S_2") (pintype "passive"))
      (node (ref "R051") (pin "1") (pinfunction "1_1") (pintype "passive"))
      (node (ref "R401") (pin "1") (pinfunction "1_1") (pintype "passive"))
      (node (ref "R401") (pin "2") (pinfunction "1_2") (pintype "passive"))
      (node (ref "R401") (pin "3") (pinfunction "1_3") (pintype "passive"))
      (node (ref "R401") (pin "4") (pinfunction "1_4") (pintype "passive"))
      (node (ref "S401") (pin "2") (pinfunction "2_2") (pintype "passive"))
      (node (ref "U101") (pin "3") (pinfunction "VCC_3") (pintype "bidirectional"))
      (node (ref "U201") (pin "5") (pinfunction "VOUT_5") (pintype "bidirectional"))
      (node (ref "U401") (pin "10") (pinfunction "VDDA_10") (pintype "bidirectional"))
      (node (ref "U401") (pin "12") (pinfunction "VREF_12") (pintype "bidirectional"))
      (node (ref "U401") (pin "13") (pinfunction "VDD(DCDC)0_13") (pintype "bidirectional"))
      (node (ref "U401") (pin "19") (pinfunction "VBAT_19") (pintype "bidirectional"))
      (node (ref "U401") (pin "28") (pinfunction "VDD(3V3)0_28") (pintype "bidirectional"))
      (node (ref "U401") (pin "42") (pinfunction "VDD(DCDC)1_42") (pintype "bidirectional"))
      (node (ref "U401") (pin "54") (pinfunction "VDD(3V3)1_54") (pintype "bidirectional"))
      (node (ref "U401") (pin "71") (pinfunction "VDD(3V3)2_71") (pintype "bidirectional"))
      (node (ref "U401") (pin "84") (pinfunction "VDD(DCDC)2_84") (pintype "bidirectional"))
      (node (ref "U401") (pin "96") (pinfunction "VDD(3V3)3_96") (pintype "bidirectional"))
      (node (ref "U402") (pin "1") (pinfunction "VCC_1") (pintype "bidirectional"))
    )
    (net (code "64") (name "unconnected-(J701-CD-PadCD1)") (class "Default")
      (node (ref "J701") (pin "CD1") (pinfunction "CD_CD1") (pintype "bidirectional"))
    )
    (net (code "65") (name "unconnected-(U401-#RSTOUT-Pad14)") (class "Default")
      (node (ref "U401") (pin "14") (pinfunction "#RSTOUT_14") (pintype "bidirectional"))
    )
    (net (code "66") (name "unconnected-(U401-#TRST-Pad4)") (class "Default")
      (node (ref "U401") (pin "4") (pinfunction "#TRST_4") (pintype "bidirectional"))
    )
    (net (code "67") (name "unconnected-(U401-P0[4]{slash}I2SRX_CLK{slash}RD2{slash}CAP2[0]-Pad81)") (class "Default")
      (node (ref "U401") (pin "81") (pinfunction "P0[4]/I2SRX_CLK/RD2/CAP2[0]_81") (pintype "bidirectional"))
    )
    (net (code "68") (name "unconnected-(U401-P0[5]{slash}I2SRX_WS{slash}TD2{slash}CAP2[1]-Pad80)") (class "Default")
      (node (ref "U401") (pin "80") (pinfunction "P0[5]/I2SRX_WS/TD2/CAP2[1]_80") (pintype "bidirectional"))
    )
    (net (code "69") (name "unconnected-(U401-P0[10]{slash}TXD2{slash}SDA2{slash}MAT3[0]-Pad48)") (class "Default")
      (node (ref "U401") (pin "48") (pinfunction "P0[10]/TXD2/SDA2/MAT3[0]_48") (pintype "bidirectional"))
    )
    (net (code "70") (name "unconnected-(U401-P0[11]{slash}RXD2{slash}SCL2{slash}MAT3[1]-Pad49)") (class "Default")
      (node (ref "U401") (pin "49") (pinfunction "P0[11]/RXD2/SCL2/MAT3[1]_49") (pintype "bidirectional"))
    )
    (net (code "71") (name "unconnected-(U401-P0[17]{slash}CTS1{slash}MISO0{slash}MISO-Pad61)") (class "Default")
      (node (ref "U401") (pin "61") (pinfunction "P0[17]/CTS1/MISO0/MISO_61") (pintype "bidirectional"))
    )
    (net (code "72") (name "unconnected-(U401-P0[18]{slash}DCD1{slash}MOSI0{slash}MOSI-Pad60)") (class "Default")
      (node (ref "U401") (pin "60") (pinfunction "P0[18]/DCD1/MOSI0/MOSI_60") (pintype "bidirectional"))
    )
    (net (code "73") (name "unconnected-(U401-P0[21]{slash}RI1{slash}MCIPWR{slash}RD1-Pad57)") (class "Default")
      (node (ref "U401") (pin "57") (pinfunction "P0[21]/RI1/MCIPWR/RD1_57") (pintype "bidirectional"))
    )
    (net (code "74") (name "unconnected-(U401-P1[4]{slash}ENET_TX_EN-Pad93)") (class "Default")
      (node (ref "U401") (pin "93") (pinfunction "P1[4]/ENET_TX_EN_93") (pintype "bidirectional"))
    )
    (net (code "75") (name "unconnected-(U401-P1[8]{slash}ENET_CRS-Pad92)") (class "Default")
      (node (ref "U401") (pin "92") (pinfunction "P1[8]/ENET_CRS_92") (pintype "bidirectional"))
    )
    (net (code "76") (name "unconnected-(U401-P1[9]{slash}ENET_RXD0-Pad91)") (class "Default")
      (node (ref "U401") (pin "91") (pinfunction "P1[9]/ENET_RXD0_91") (pintype "bidirectional"))
    )
    (net (code "77") (name "unconnected-(U401-P1[10]{slash}ENET_RXD1-Pad90)") (class "Default")
      (node (ref "U401") (pin "90") (pinfunction "P1[10]/ENET_RXD1_90") (pintype "bidirectional"))
    )
    (net (code "78") (name "unconnected-(U401-P1[14]{slash}ENET_RX_ER-Pad89)") (class "Default")
      (node (ref "U401") (pin "89") (pinfunction "P1[14]/ENET_RX_ER_89") (pintype "bidirectional"))
    )
    (net (code "79") (name "unconnected-(U401-P1[15]{slash}ENET_REF_CLK-Pad88)") (class "Default")
      (node (ref "U401") (pin "88") (pinfunction "P1[15]/ENET_REF_CLK_88") (pintype "bidirectional"))
    )
    (net (code "80") (name "unconnected-(U401-P1[16]{slash}ENET_MDC-Pad87)") (class "Default")
      (node (ref "U401") (pin "87") (pinfunction "P1[16]/ENET_MDC_87") (pintype "bidirectional"))
    )
    (net (code "81") (name "unconnected-(U401-P1[17]{slash}ENET_MDIO-Pad86)") (class "Default")
      (node (ref "U401") (pin "86") (pinfunction "P1[17]/ENET_MDIO_86") (pintype "bidirectional"))
    )
    (net (code "82") (name "unconnected-(U401-P1[19]{slash}CAP1[1]-Pad33)") (class "Default")
      (node (ref "U401") (pin "33") (pinfunction "P1[19]/CAP1[1]_33") (pintype "bidirectional"))
    )
    (net (code "83") (name "unconnected-(U401-P1[20]{slash}PWM1[2]{slash}SCK0-Pad34)") (class "Default")
      (node (ref "U401") (pin "34") (pinfunction "P1[20]/PWM1[2]/SCK0_34") (pintype "bidirectional"))
    )
    (net (code "84") (name "unconnected-(U401-P1[21]{slash}PWM1[3]{slash}SSEL0-Pad35)") (class "Default")
      (node (ref "U401") (pin "35") (pinfunction "P1[21]/PWM1[3]/SSEL0_35") (pintype "bidirectional"))
    )
    (net (code "85") (name "unconnected-(U401-P1[22]{slash}MAT1[0]-Pad36)") (class "Default")
      (node (ref "U401") (pin "36") (pinfunction "P1[22]/MAT1[0]_36") (pintype "bidirectional"))
    )
    (net (code "86") (name "unconnected-(U401-P1[23]{slash}PWM1[4]{slash}MISO0-Pad37)") (class "Default")
      (node (ref "U401") (pin "37") (pinfunction "P1[23]/PWM1[4]/MISO0_37") (pintype "bidirectional"))
    )
    (net (code "87") (name "unconnected-(U401-P1[24]{slash}PWM1[5]{slash}MOSI0-Pad38)") (class "Default")
      (node (ref "U401") (pin "38") (pinfunction "P1[24]/PWM1[5]/MOSI0_38") (pintype "bidirectional"))
    )
    (net (code "88") (name "unconnected-(U401-P1[25]{slash}MAT1[1]-Pad39)") (class "Default")
      (node (ref "U401") (pin "39") (pinfunction "P1[25]/MAT1[1]_39") (pintype "bidirectional"))
    )
    (net (code "89") (name "unconnected-(U401-P1[28]{slash}PCAP1[0]{slash}MAT0[0]-Pad44)") (class "Default")
      (node (ref "U401") (pin "44") (pinfunction "P1[28]/PCAP1[0]/MAT0[0]_44") (pintype "bidirectional"))
    )
    (net (code "90") (name "unconnected-(U401-P1[29]{slash}PCAP1[1]{slash}MAT0[1]-Pad45)") (class "Default")
      (node (ref "U401") (pin "45") (pinfunction "P1[29]/PCAP1[1]/MAT0[1]_45") (pintype "bidirectional"))
    )
    (net (code "91") (name "unconnected-(U401-P2[6]{slash}PCAP1[0]{slash}RI1{slash}TRACEPKT1-Pad67)") (class "Default")
      (node (ref "U401") (pin "67") (pinfunction "P2[6]/PCAP1[0]/RI1/TRACEPKT1_67") (pintype "bidirectional"))
    )
    (net (code "92") (name "unconnected-(U401-P2[7]{slash}RD2{slash}RTS1{slash}TRACEPKT2-Pad66)") (class "Default")
      (node (ref "U401") (pin "66") (pinfunction "P2[7]/RD2/RTS1/TRACEPKT2_66") (pintype "bidirectional"))
    )
    (net (code "93") (name "unconnected-(U401-P2[8]{slash}TD2{slash}TXD2{slash}TRACEPKT3-Pad65)") (class "Default")
      (node (ref "U401") (pin "65") (pinfunction "P2[8]/TD2/TXD2/TRACEPKT3_65") (pintype "bidirectional"))
    )
    (net (code "94") (name "unconnected-(U401-P3[25]{slash}MAT0[0]{slash}PWM1[2]-Pad27)") (class "Default")
      (node (ref "U401") (pin "27") (pinfunction "P3[25]/MAT0[0]/PWM1[2]_27") (pintype "bidirectional"))
    )
    (net (code "95") (name "unconnected-(U401-P3[26]{slash}MAT0[1]{slash}PWM1[3]-Pad26)") (class "Default")
      (node (ref "U401") (pin "26") (pinfunction "P3[26]/MAT0[1]/PWM1[3]_26") (pintype "bidirectional"))
    )
    (net (code "96") (name "unconnected-(U401-P4[28]{slash}MAT2[0]{slash}TXD3-Pad82)") (class "Default")
      (node (ref "U401") (pin "82") (pinfunction "P4[28]/MAT2[0]/TXD3_82") (pintype "bidirectional"))
    )
    (net (code "97") (name "unconnected-(U401-P4[29]{slash}MAT2[1]{slash}RXD3-Pad85)") (class "Default")
      (node (ref "U401") (pin "85") (pinfunction "P4[29]/MAT2[1]/RXD3_85") (pintype "bidirectional"))
    )
    (net (code "98") (name "unconnected-(U401-RTCK-Pad100)") (class "Default")
      (node (ref "U401") (pin "100") (pinfunction "RTCK_100") (pintype "bidirectional"))
    )
    (net (code "99") (name "unconnected-(U401-RTCX1-Pad16)") (class "Default")
      (node (ref "U401") (pin "16") (pinfunction "RTCX1_16") (pintype "bidirectional"))
    )
    (net (code "100") (name "unconnected-(U401-RTCX2-Pad18)") (class "Default")
      (node (ref "U401") (pin "18") (pinfunction "RTCX2_18") (pintype "bidirectional"))
    )
    (net (code "101") (name "unconnected-(U401-TCK-Pad5)") (class "Default")
      (node (ref "U401") (pin "5") (pinfunction "TCK_5") (pintype "bidirectional"))
    )
    (net (code "102") (name "unconnected-(U401-TD0-Pad1)") (class "Default")
      (node (ref "U401") (pin "1") (pinfunction "TD0_1") (pintype "bidirectional"))
    )
    (net (code "103") (name "unconnected-(U401-TDI-Pad2)") (class "Default")
      (node (ref "U401") (pin "2") (pinfunction "TDI_2") (pintype "bidirectional"))
    )
    (net (code "104") (name "unconnected-(U401-TMS-Pad3)") (class "Default")
      (node (ref "U401") (pin "3") (pinfunction "TMS_3") (pintype "bidirectional"))
    )
  )
)
